# Enclosure_100x68_BHCP.net
KiCad netlist of a schematic drawn in EAGLE
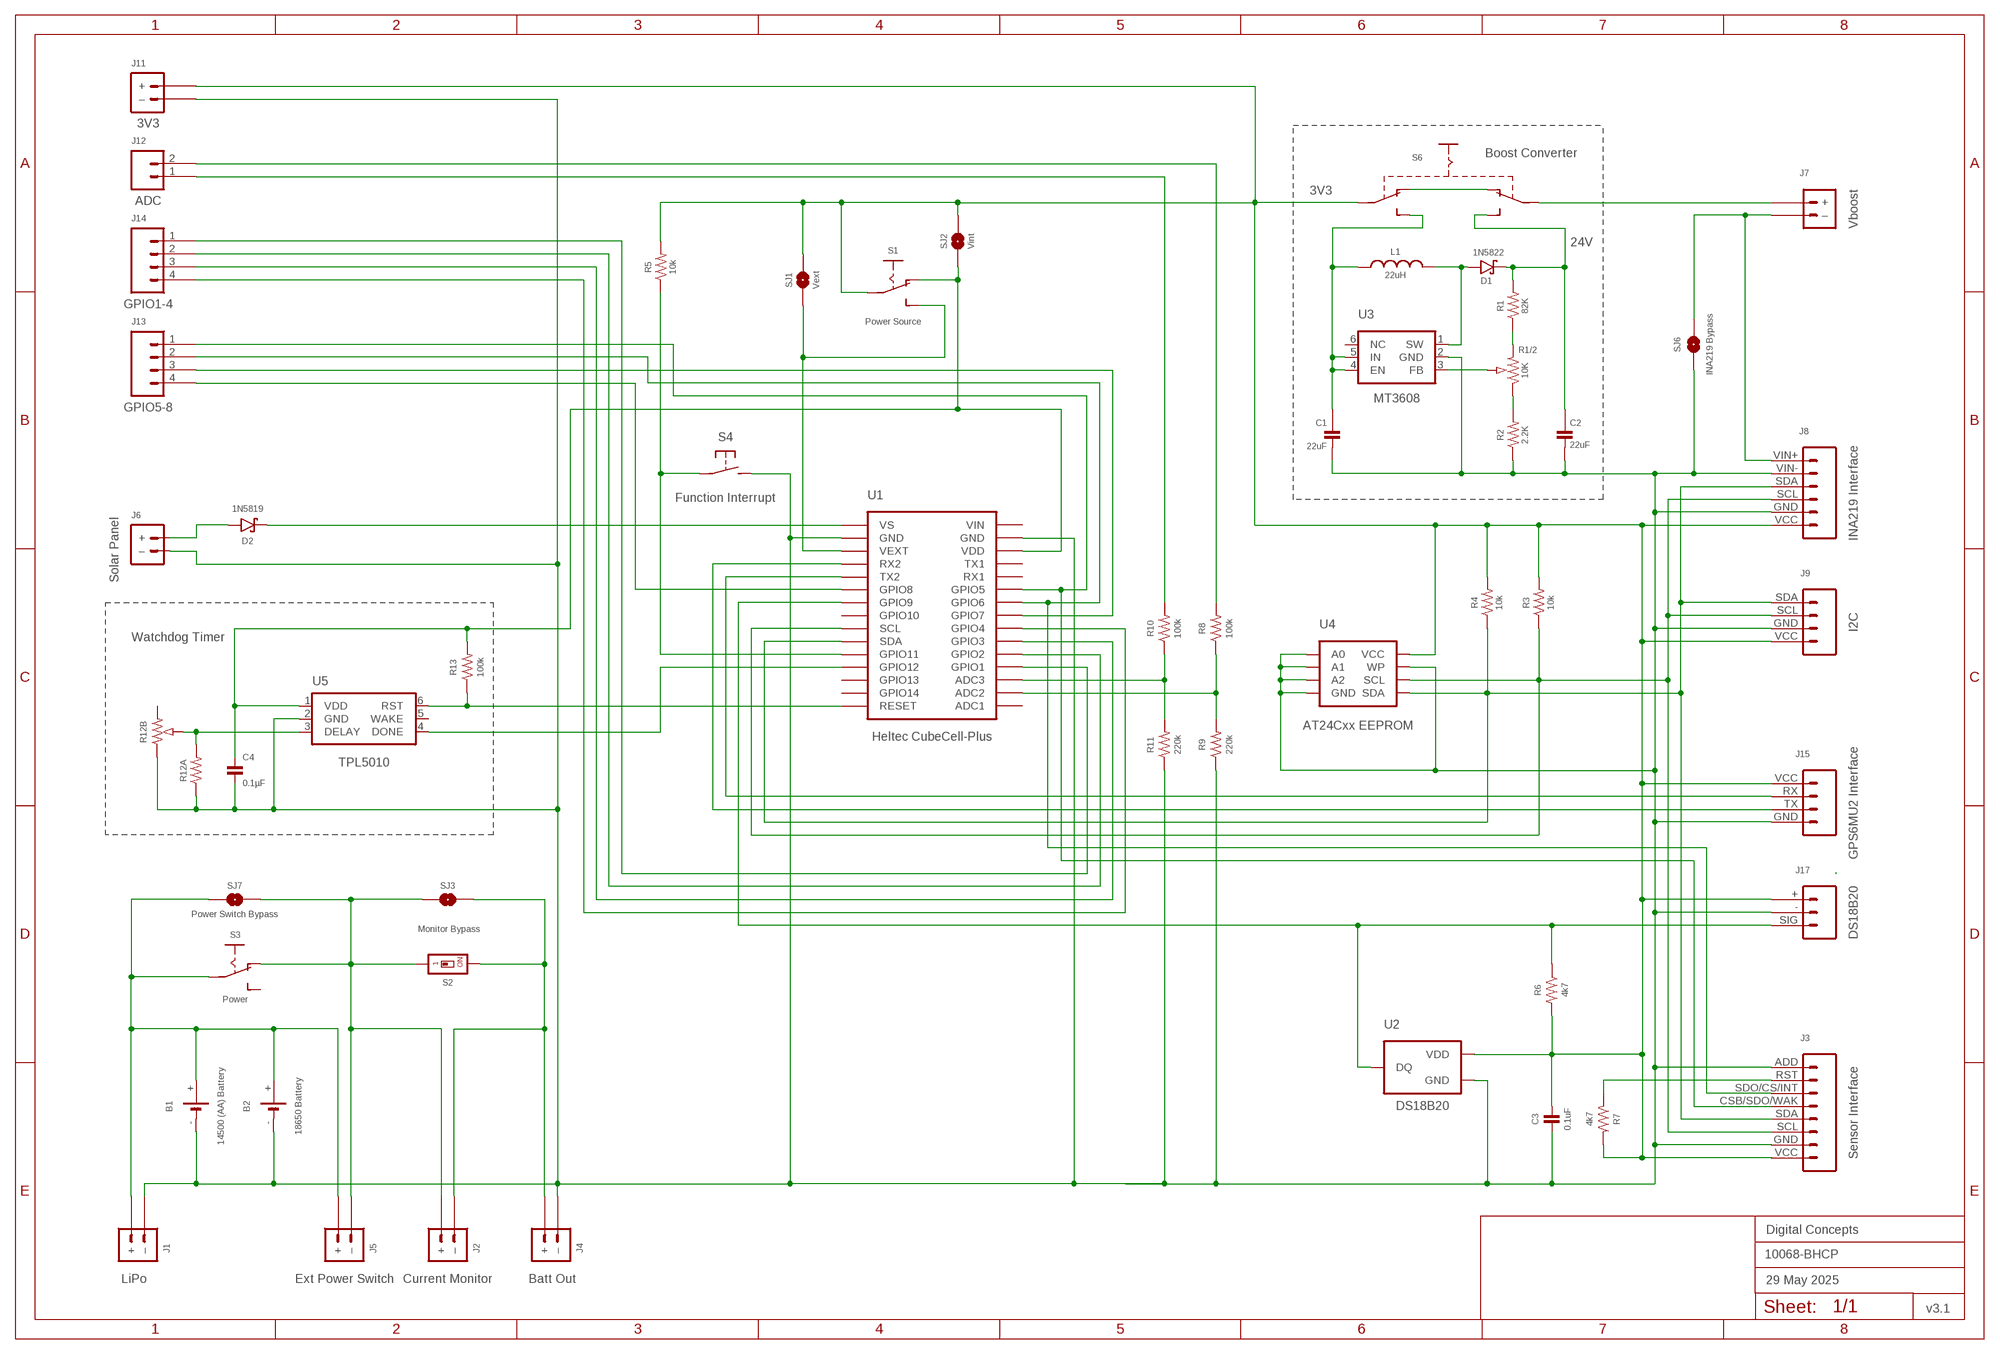
[diagram p0: schematic, sheet 1]

(export (version "E")
  (design (tool "Eeschema 10.0.6"))
  (components
    (comp (ref "B1")
      (value "14500 (AA) Battery")
      (footprint "eagle-import:BATTERY-14500")
      (libsource (lib "eagle-import") (part "BATTERY-HOLDER-14500(AA)"))
    )
    (comp (ref "B2")
      (value "18650 Battery")
      (footprint "eagle-import:BATTERY-18650")
      (libsource (lib "eagle-import") (part "BATTERY-HOLDER-18650"))
    )
    (comp (ref "C1")
      (value "22uF")
      (footprint "eagle-import:C1206")
      (libsource (lib "eagle-import") (part "CAPACITOR-1206"))
    )
    (comp (ref "C2")
      (value "22uF")
      (footprint "eagle-import:C1206")
      (libsource (lib "eagle-import") (part "CAPACITOR-1206"))
    )
    (comp (ref "C3")
      (value "0.1uF")
      (footprint "eagle-import:C0805")
      (libsource (lib "eagle-import") (part "CAPACITOR-0805"))
    )
    (comp (ref "C4")
      (value "0.1µF")
      (footprint "eagle-import:C0805")
      (libsource (lib "eagle-import") (part "CAPACITOR-0805"))
    )
    (comp (ref "D1")
      (value "1N5822")
      (footprint "eagle-import:DIODE_SMB")
      (libsource (lib "eagle-import") (part "DIODE-SCHOTTKY-1N5822"))
    )
    (comp (ref "D2")
      (value "1N5819")
      (footprint "eagle-import:SOD-123")
      (libsource (lib "eagle-import") (part "1N5819-SOD-123"))
    )
    (comp (ref "J1")
      (value "LiPo")
      (footprint "eagle-import:JST-PH2.0-2-HORIZONTAL-POWER")
      (libsource (lib "eagle-import") (part "JST-PH2.0-2-H-POWER"))
    )
    (comp (ref "J2")
      (value "Current Monitor")
      (footprint "eagle-import:JST-PH2.0-2-HORIZONTAL-POWER")
      (libsource (lib "eagle-import") (part "JST-PH2.0-2-H-POWER"))
    )
    (comp (ref "J3")
      (value "Sensor Interface")
      (footprint "eagle-import:CONN_08-SENSOR")
      (libsource (lib "eagle-import") (part "HEADER-1X8-SENSOR"))
    )
    (comp (ref "J4")
      (value "Batt Out")
      (footprint "eagle-import:JST-GH1.25-2-HORIZONTAL")
      (libsource (lib "eagle-import") (part "JST-GH1.25-2-HORIZONTAL-POWER"))
    )
    (comp (ref "J5")
      (value "Ext Power Switch")
      (footprint "eagle-import:JST-PH2.0-2-DUAL-POWER")
      (libsource (lib "eagle-import") (part "JST-PH2.0-2-DUAL-POWER{dblquote}"))
    )
    (comp (ref "J6")
      (value "Solar Panel")
      (footprint "eagle-import:JST-PH2.0-2-VERTICAL=POWER")
      (libsource (lib "eagle-import") (part "JST-PH2.0-2-VERTICAL"))
    )
    (comp (ref "J7")
      (value "Vboost")
      (footprint "eagle-import:JST-PH2.0-2-HORIZONTAL-POWER")
      (libsource (lib "eagle-import") (part "JST-PH2.0-2-H-POWER"))
    )
    (comp (ref "J8")
      (value "INA219 Interface")
      (footprint "eagle-import:CONN_06-INA219")
      (libsource (lib "eagle-import") (part "INA219-I2C-MODULE"))
    )
    (comp (ref "J9")
      (value "I2C")
      (footprint "eagle-import:JST-PH2.0-4-HORIZONTAL@1")
      (libsource (lib "eagle-import") (part "JST-PH2.0-I2C-MALE-HORIZONTAL"))
    )
    (comp (ref "J11")
      (value "3V3")
      (footprint "eagle-import:JST-PH2.0-2-HORIZONTAL-POWER")
      (libsource (lib "eagle-import") (part "JST-PH2.0-2-H-POWER"))
    )
    (comp (ref "J12")
      (value "ADC")
      (footprint "eagle-import:JST-PH2.0-2-HORIZONTAL")
      (libsource (lib "eagle-import") (part "JST-PH2.0-2-HORIZONTAL"))
    )
    (comp (ref "J13")
      (value "GPIO5-8")
      (footprint "eagle-import:JST-PH2.0-4-HORIZONTAL")
      (libsource (lib "eagle-import") (part "JST-PH2.0-4-HORIZONTAL"))
    )
    (comp (ref "J14")
      (value "GPIO1-4")
      (footprint "eagle-import:JST-PH2.0-4-HORIZONTAL")
      (libsource (lib "eagle-import") (part "JST-PH2.0-4-HORIZONTAL"))
    )
    (comp (ref "J15")
      (value "GPS6MU2 Interface")
      (footprint "eagle-import:CONN_04-GPS")
      (libsource (lib "eagle-import") (part "HEADER-1X4-GPS"))
    )
    (comp (ref "J17")
      (value "DS18B20")
      (footprint "eagle-import:JST-PH2.0-DS18B20-HORIZONTAL")
      (libsource (lib "eagle-import") (part "JST-PH2.0-3-HORIZONTAL-DS18B20"))
    )
    (comp (ref "L1")
      (value "22uH")
      (footprint "eagle-import:CDRH104R+6D28")
      (libsource (lib "eagle-import") (part "INDUCTOR-CDRH104R/6D28L5038P"))
    )
    (comp (ref "R1")
      (value "82K")
      (footprint "eagle-import:R0805")
      (libsource (lib "eagle-import") (part "RESISTORR0805"))
    )
    (comp (ref "R1/2")
      (value "10K")
      (footprint "eagle-import:RTRIM64P")
      (libsource (lib "eagle-import") (part "RESISTOR-TRIMM-BAOTER-H-US"))
    )
    (comp (ref "R2")
      (value "2.2K")
      (footprint "eagle-import:R0805")
      (libsource (lib "eagle-import") (part "RESISTORR0805"))
    )
    (comp (ref "R3")
      (value "10k")
      (footprint "eagle-import:R0805")
      (libsource (lib "eagle-import") (part "RESISTORR0805"))
    )
    (comp (ref "R4")
      (value "10k")
      (footprint "eagle-import:R0805")
      (libsource (lib "eagle-import") (part "RESISTORR0805"))
    )
    (comp (ref "R5")
      (value "10k")
      (footprint "eagle-import:R0805")
      (libsource (lib "eagle-import") (part "RESISTORR0805"))
    )
    (comp (ref "R6")
      (value "4k7")
      (footprint "eagle-import:R0805")
      (libsource (lib "eagle-import") (part "RESISTORR0805"))
    )
    (comp (ref "R7")
      (value "4k7")
      (footprint "eagle-import:R0805")
      (libsource (lib "eagle-import") (part "RESISTORR0805"))
    )
    (comp (ref "R8")
      (value "100k")
      (footprint "eagle-import:R0805")
      (libsource (lib "eagle-import") (part "RESISTORR0805"))
    )
    (comp (ref "R9")
      (value "220k")
      (footprint "eagle-import:R0805")
      (libsource (lib "eagle-import") (part "RESISTORR0805"))
    )
    (comp (ref "R10")
      (value "100k")
      (footprint "eagle-import:R0805")
      (libsource (lib "eagle-import") (part "RESISTORR0805"))
    )
    (comp (ref "R11")
      (value "220k")
      (footprint "eagle-import:R0805")
      (libsource (lib "eagle-import") (part "RESISTORR0805"))
    )
    (comp (ref "R12A")
      (value "RESISTORR0805")
      (footprint "eagle-import:R0805")
      (libsource (lib "eagle-import") (part "RESISTORR0805"))
    )
    (comp (ref "R12B")
      (value "RESISTOR-TRIMM-33-US")
      (footprint "eagle-import:RTRIM3_3")
      (libsource (lib "eagle-import") (part "RESISTOR-TRIMM-33-US"))
    )
    (comp (ref "R13")
      (value "100k")
      (footprint "eagle-import:R0805")
      (libsource (lib "eagle-import") (part "RESISTORR0805"))
    )
    (comp (ref "S1")
      (value "Power Source")
      (footprint "eagle-import:SWITCH-SPDT-SMT")
      (libsource (lib "eagle-import") (part "SWITCH-SLIDE-SPDT-SMT"))
    )
    (comp (ref "S2")
      (value "Monitor Bypass")
      (footprint "eagle-import:SMD-001")
      (libsource (lib "eagle-import") (part "SWITCH-DIP-SWS001"))
    )
    (comp (ref "S3")
      (value "Power")
      (footprint "eagle-import:SWITCH-SPDT-PTH")
      (libsource (lib "eagle-import") (part "SWITCH-SLIDE-SPDT-PTH"))
    )
    (comp (ref "S4")
      (value "Function Interrupt")
      (footprint "eagle-import:SWITCH-2-PAD")
      (libsource (lib "eagle-import") (part "SWITCH-MOMENTARY-2-PIN"))
    )
    (comp (ref "S6")
      (value "SWITCH-SLIDE-DPDT-PTH-S")
      (footprint "eagle-import:SWITCH-DPDT-PTH")
      (libsource (lib "eagle-import") (part "SWITCH-SLIDE-DPDT-PTH-S"))
    )
    (comp (ref "SJ1")
      (value "Vext")
      (footprint "eagle-import:SJ")
      (libsource (lib "eagle-import") (part "SJ"))
    )
    (comp (ref "SJ2")
      (value "Vint")
      (footprint "eagle-import:SJ-VIA-12")
      (libsource (lib "eagle-import") (part "SJ-V-12"))
    )
    (comp (ref "SJ3")
      (value "Monitor")
      (footprint "eagle-import:SJ")
      (libsource (lib "eagle-import") (part "SJ"))
    )
    (comp (ref "SJ6")
      (value "INA219 Bypass")
      (footprint "eagle-import:SJ")
      (libsource (lib "eagle-import") (part "SJ"))
    )
    (comp (ref "SJ7")
      (value "Power Switch Bypass")
      (footprint "eagle-import:SJ")
      (libsource (lib "eagle-import") (part "SJ"))
    )
    (comp (ref "U1")
      (value "Heltec CubeCell-Plus")
      (footprint "eagle-import:HELTEC-CUBECELL=PLUS-X")
      (libsource (lib "eagle-import") (part "HELTEC-CUBECELL-PLUS-X"))
    )
    (comp (ref "U2")
      (value "DS18B20")
      (footprint "eagle-import:TO-92")
      (fields (field (name "MF") "Maxim Integrated"))
      (libsource (lib "eagle-import") (part "THERMOMETER-DS18B20"))
    )
    (comp (ref "U3")
      (value "MT3608")
      (footprint "eagle-import:SOT-23-6")
      (libsource (lib "eagle-import") (part "MT3608"))
    )
    (comp (ref "U4")
      (value "AT24Cxx EEPROM")
      (footprint "eagle-import:SOP-8")
      (libsource (lib "eagle-import") (part "AT24CXX-EEPROM"))
    )
    (comp (ref "U5")
      (value "TPL5010")
      (footprint "eagle-import:SOT-23-6")
      (libsource (lib "eagle-import") (part "TPL5010DDCR"))
    )
  )
  (nets
    (net (code "1") (name "/VIN") (class "Default")
      (node (ref "U1") (pin "VIN") (pinfunction "VIN_VIN") (pintype "power_in"))
    )
    (net (code "2") (name "Net-(D2-PadA)") (class "Default")
      (node (ref "D2") (pin "A") (pinfunction "A_A") (pintype "passive"))
      (node (ref "J6") (pin "+") (pinfunction "+_+") (pintype "power_in"))
    )
    (net (code "3") (name "Net-(D2-PadC)") (class "Default")
      (node (ref "D2") (pin "C") (pinfunction "C_C") (pintype "passive"))
      (node (ref "U1") (pin "VS") (pinfunction "VS_VS") (pintype "power_in"))
    )
    (net (code "4") (name "Net-(J1-–)") (class "Default")
      (node (ref "B1") (pin "-") (pinfunction "-_-") (pintype "power_in"))
      (node (ref "B2") (pin "-") (pinfunction "-_-") (pintype "power_in"))
      (node (ref "C1") (pin "2") (pinfunction "2_2") (pintype "passive"))
      (node (ref "C2") (pin "2") (pinfunction "2_2") (pintype "passive"))
      (node (ref "C3") (pin "2") (pinfunction "2_2") (pintype "passive"))
      (node (ref "C4") (pin "2") (pinfunction "2_2") (pintype "passive"))
      (node (ref "J1") (pin "-") (pinfunction "–_-") (pintype "power_in"))
      (node (ref "J11") (pin "-") (pinfunction "–_-") (pintype "power_in"))
      (node (ref "J15") (pin "GND") (pinfunction "1_GND") (pintype "passive"))
      (node (ref "J17") (pin "-") (pinfunction "2_-") (pintype "passive"))
      (node (ref "J3") (pin "ADD") (pinfunction "8_ADD") (pintype "passive"))
      (node (ref "J3") (pin "GND") (pinfunction "2_GND") (pintype "passive"))
      (node (ref "J4") (pin "-") (pinfunction "–_-") (pintype "power_in"))
      (node (ref "J6") (pin "-") (pinfunction "–_-") (pintype "power_in"))
      (node (ref "J8") (pin "GND") (pinfunction "2_GND") (pintype "passive"))
      (node (ref "J8") (pin "VIN-") (pinfunction "5_VIN-") (pintype "passive"))
      (node (ref "J9") (pin "GND") (pinfunction "2_GND") (pintype "passive"))
      (node (ref "R11") (pin "1") (pinfunction "1_1") (pintype "passive"))
      (node (ref "R12A") (pin "1") (pinfunction "1_1") (pintype "passive"))
      (node (ref "R12B") (pin "1") (pinfunction "A_1") (pintype "passive"))
      (node (ref "R2") (pin "1") (pinfunction "1_1") (pintype "passive"))
      (node (ref "R9") (pin "1") (pinfunction "1_1") (pintype "passive"))
      (node (ref "S4") (pin "P$2") (pinfunction "S_P$2") (pintype "passive"))
      (node (ref "SJ6") (pin "1") (pinfunction "1_1") (pintype "passive"))
      (node (ref "U1") (pin "GND@14") (pinfunction "GND_GND@14") (pintype "power_in"))
      (node (ref "U1") (pin "GND@17") (pinfunction "GND_GND@17") (pintype "power_in"))
      (node (ref "U2") (pin "1") (pinfunction "GND_1") (pintype "power_in"))
      (node (ref "U3") (pin "2") (pinfunction "GND_2") (pintype "power_in"))
      (node (ref "U4") (pin "P$1") (pinfunction "A0_P$1") (pintype "bidirectional"))
      (node (ref "U4") (pin "P$2") (pinfunction "A1_P$2") (pintype "bidirectional"))
      (node (ref "U4") (pin "P$3") (pinfunction "A2_P$3") (pintype "bidirectional"))
      (node (ref "U4") (pin "P$4") (pinfunction "GND_P$4") (pintype "bidirectional"))
      (node (ref "U4") (pin "P$7") (pinfunction "WP_P$7") (pintype "bidirectional"))
      (node (ref "U5") (pin "2") (pinfunction "GND_2") (pintype "power_in"))
    )
    (net (code "5") (name "Net-(J2-–)") (class "Default")
      (node (ref "J2") (pin "-") (pinfunction "–_-") (pintype "power_in"))
      (node (ref "J4") (pin "+") (pinfunction "+_+") (pintype "power_in"))
      (node (ref "S2") (pin "2") (pinfunction "2_2") (pintype "passive"))
      (node (ref "SJ3") (pin "1") (pinfunction "1_1") (pintype "passive"))
    )
    (net (code "6") (name "Net-(J3-3)") (class "Default")
      (node (ref "J3") (pin "SCL") (pinfunction "3_SCL") (pintype "passive"))
      (node (ref "J8") (pin "SCL") (pinfunction "3_SCL") (pintype "passive"))
      (node (ref "J9") (pin "SCL") (pinfunction "3_SCL") (pintype "passive"))
      (node (ref "R3") (pin "1") (pinfunction "1_1") (pintype "passive"))
      (node (ref "U1") (pin "SCL") (pinfunction "SCL_SCL") (pintype "bidirectional"))
      (node (ref "U4") (pin "P$6") (pinfunction "SCL_P$6") (pintype "bidirectional"))
    )
    (net (code "7") (name "Net-(J3-4)") (class "Default")
      (node (ref "J3") (pin "SDA") (pinfunction "4_SDA") (pintype "passive"))
      (node (ref "J8") (pin "SDA") (pinfunction "4_SDA") (pintype "passive"))
      (node (ref "J9") (pin "SDA") (pinfunction "4_SDA") (pintype "passive"))
      (node (ref "R4") (pin "1") (pinfunction "1_1") (pintype "passive"))
      (node (ref "U1") (pin "SDA") (pinfunction "SDA_SDA") (pintype "bidirectional"))
      (node (ref "U4") (pin "P$5") (pinfunction "SDA_P$5") (pintype "bidirectional"))
    )
    (net (code "8") (name "Net-(J3-7)") (class "Default")
      (node (ref "J3") (pin "RST") (pinfunction "7_RST") (pintype "passive"))
      (node (ref "R7") (pin "1") (pinfunction "1_1") (pintype "passive"))
    )
    (net (code "9") (name "Net-(J5-–)") (class "Default")
      (node (ref "J2") (pin "+") (pinfunction "+_+") (pintype "power_in"))
      (node (ref "J5") (pin "-") (pinfunction "–_-") (pintype "power_in"))
      (node (ref "S2") (pin "1") (pinfunction "1_1") (pintype "passive"))
      (node (ref "S3") (pin "1") (pinfunction "O_1") (pintype "passive"))
      (node (ref "SJ3") (pin "2") (pinfunction "2_2") (pintype "passive"))
      (node (ref "SJ7") (pin "1") (pinfunction "1_1") (pintype "passive"))
    )
    (net (code "10") (name "Net-(J7-–)") (class "Default")
      (node (ref "J7") (pin "-") (pinfunction "–_-") (pintype "power_in"))
      (node (ref "J8") (pin "VIN+") (pinfunction "6_VIN+") (pintype "passive"))
      (node (ref "SJ6") (pin "2") (pinfunction "2_2") (pintype "passive"))
    )
    (net (code "11") (name "Net-(J12-Pad1)") (class "Default")
      (node (ref "J12") (pin "1") (pinfunction "1_1") (pintype "passive"))
      (node (ref "R10") (pin "2") (pinfunction "2_2") (pintype "passive"))
    )
    (net (code "12") (name "Net-(J12-Pad2)") (class "Default")
      (node (ref "J12") (pin "2") (pinfunction "2_2") (pintype "passive"))
      (node (ref "R8") (pin "2") (pinfunction "2_2") (pintype "passive"))
    )
    (net (code "13") (name "Net-(J13-1)") (class "Default")
      (node (ref "J13") (pin "4") (pinfunction "1_4") (pintype "passive"))
      (node (ref "U1") (pin "GPIO8") (pinfunction "GPIO8_GPIO8") (pintype "bidirectional"))
    )
    (net (code "14") (name "Net-(J13-2)") (class "Default")
      (node (ref "J13") (pin "3") (pinfunction "2_3") (pintype "passive"))
      (node (ref "U1") (pin "GPIO7") (pinfunction "GPIO7_GPIO7") (pintype "bidirectional"))
    )
    (net (code "15") (name "Net-(J13-3)") (class "Default")
      (node (ref "J13") (pin "2") (pinfunction "3_2") (pintype "passive"))
      (node (ref "J3") (pin "SDO/CS/INT") (pinfunction "6_SDO/CS/INT") (pintype "passive"))
      (node (ref "U1") (pin "GPIO6") (pinfunction "GPIO6_GPIO6") (pintype "bidirectional"))
    )
    (net (code "16") (name "Net-(J13-4)") (class "Default")
      (node (ref "J13") (pin "1") (pinfunction "4_1") (pintype "passive"))
      (node (ref "J3") (pin "CSB/SDO/WAK") (pinfunction "5_CSB/SDO/WAK") (pintype "passive"))
      (node (ref "U1") (pin "GPIO5") (pinfunction "GPIO5_GPIO5") (pintype "bidirectional"))
    )
    (net (code "17") (name "Net-(J14-1)") (class "Default")
      (node (ref "J14") (pin "4") (pinfunction "1_4") (pintype "passive"))
      (node (ref "U1") (pin "GPIO4") (pinfunction "GPIO4_GPIO4") (pintype "bidirectional"))
    )
    (net (code "18") (name "Net-(J14-2)") (class "Default")
      (node (ref "J14") (pin "3") (pinfunction "2_3") (pintype "passive"))
      (node (ref "U1") (pin "GPIO3") (pinfunction "GPIO3_GPIO3") (pintype "bidirectional"))
    )
    (net (code "19") (name "Net-(J14-3)") (class "Default")
      (node (ref "J14") (pin "2") (pinfunction "3_2") (pintype "passive"))
      (node (ref "U1") (pin "GPIO2") (pinfunction "GPIO2_GPIO2") (pintype "bidirectional"))
    )
    (net (code "20") (name "Net-(J14-4)") (class "Default")
      (node (ref "J14") (pin "1") (pinfunction "4_1") (pintype "passive"))
      (node (ref "U1") (pin "GPIO1") (pinfunction "GPIO1_GPIO1") (pintype "bidirectional"))
    )
    (net (code "21") (name "Net-(J15-2)") (class "Default")
      (node (ref "J15") (pin "TX") (pinfunction "2_TX") (pintype "passive"))
      (node (ref "U1") (pin "RX2") (pinfunction "RX2_RX2") (pintype "bidirectional"))
    )
    (net (code "22") (name "Net-(J15-3)") (class "Default")
      (node (ref "J15") (pin "RX") (pinfunction "3_RX") (pintype "passive"))
      (node (ref "U1") (pin "TX2") (pinfunction "TX2_TX2") (pintype "bidirectional"))
    )
    (net (code "23") (name "Net-(J15-4)") (class "Default")
      (node (ref "C3") (pin "1") (pinfunction "1_1") (pintype "passive"))
      (node (ref "J11") (pin "+") (pinfunction "+_+") (pintype "power_in"))
      (node (ref "J15") (pin "VCC") (pinfunction "4_VCC") (pintype "passive"))
      (node (ref "J17") (pin "+") (pinfunction "3_+") (pintype "passive"))
      (node (ref "J3") (pin "VCC") (pinfunction "1_VCC") (pintype "passive"))
      (node (ref "J8") (pin "VCC") (pinfunction "1_VCC") (pintype "passive"))
      (node (ref "J9") (pin "VCC") (pinfunction "1_VCC") (pintype "passive"))
      (node (ref "R3") (pin "2") (pinfunction "2_2") (pintype "passive"))
      (node (ref "R4") (pin "2") (pinfunction "2_2") (pintype "passive"))
      (node (ref "R5") (pin "2") (pinfunction "2_2") (pintype "passive"))
      (node (ref "R6") (pin "2") (pinfunction "2_2") (pintype "passive"))
      (node (ref "R7") (pin "2") (pinfunction "2_2") (pintype "passive"))
      (node (ref "S1") (pin "2") (pinfunction "P_2") (pintype "passive"))
      (node (ref "S6") (pin "P$5") (pinfunction "P2_P$5") (pintype "passive"))
      (node (ref "SJ1") (pin "2") (pinfunction "2_2") (pintype "passive"))
      (node (ref "SJ2") (pin "2") (pinfunction "2_2") (pintype "passive"))
      (node (ref "SJ2") (pin "2@V") (pinfunction "2_2@V") (pintype "passive"))
      (node (ref "U2") (pin "3") (pinfunction "VDD_3") (pintype "power_in"))
      (node (ref "U4") (pin "P$8") (pinfunction "VCC_P$8") (pintype "bidirectional"))
    )
    (net (code "24") (name "Net-(J17-1)") (class "Default")
      (node (ref "J17") (pin "SIG") (pinfunction "1_SIG") (pintype "passive"))
      (node (ref "R6") (pin "1") (pinfunction "1_1") (pintype "passive"))
      (node (ref "U1") (pin "GPIO9") (pinfunction "GPIO9_GPIO9") (pintype "bidirectional"))
      (node (ref "U2") (pin "2") (pinfunction "DQ_2") (pintype "bidirectional"))
    )
    (net (code "25") (name "Net-(R1/2-A)") (class "Default")
      (node (ref "R1/2") (pin "1") (pinfunction "A_1") (pintype "passive"))
      (node (ref "R2") (pin "2") (pinfunction "2_2") (pintype "passive"))
    )
    (net (code "26") (name "Net-(R1/2-E)") (class "Default")
      (node (ref "R1") (pin "1") (pinfunction "1_1") (pintype "passive"))
      (node (ref "R1/2") (pin "3") (pinfunction "E_3") (pintype "passive"))
    )
    (net (code "27") (name "Net-(R1/2-S)") (class "Default")
      (node (ref "R1/2") (pin "2") (pinfunction "S_2") (pintype "passive"))
      (node (ref "U3") (pin "3") (pinfunction "FB_3") (pintype "input"))
    )
    (net (code "28") (name "Net-(R8-Pad1)") (class "Default")
      (node (ref "R8") (pin "1") (pinfunction "1_1") (pintype "passive"))
      (node (ref "R9") (pin "2") (pinfunction "2_2") (pintype "passive"))
      (node (ref "U1") (pin "ADC2") (pinfunction "ADC2_ADC2") (pintype "bidirectional"))
    )
    (net (code "29") (name "Net-(R10-Pad1)") (class "Default")
      (node (ref "R10") (pin "1") (pinfunction "1_1") (pintype "passive"))
      (node (ref "R11") (pin "2") (pinfunction "2_2") (pintype "passive"))
      (node (ref "U1") (pin "ADC3") (pinfunction "ADC3_ADC3") (pintype "bidirectional"))
    )
    (net (code "30") (name "Net-(R12B-S)") (class "Default")
      (node (ref "R12A") (pin "2") (pinfunction "2_2") (pintype "passive"))
      (node (ref "R12B") (pin "2") (pinfunction "S_2") (pintype "passive"))
      (node (ref "U5") (pin "3") (pinfunction "DELAY_3") (pintype "input"))
    )
    (net (code "31") (name "Net-(S1-O)") (class "Default")
      (node (ref "C4") (pin "1") (pinfunction "1_1") (pintype "passive"))
      (node (ref "R13") (pin "2") (pinfunction "2_2") (pintype "passive"))
      (node (ref "S1") (pin "1") (pinfunction "O_1") (pintype "passive"))
      (node (ref "SJ2") (pin "1") (pinfunction "1_1") (pintype "passive"))
      (node (ref "SJ2") (pin "1@V") (pinfunction "1_1@V") (pintype "passive"))
      (node (ref "U1") (pin "VDD") (pinfunction "VDD_VDD") (pintype "power_in"))
      (node (ref "U5") (pin "1") (pinfunction "VDD_1") (pintype "power_in"))
    )
    (net (code "32") (name "Net-(S1-S)") (class "Default")
      (node (ref "S1") (pin "3") (pinfunction "S_3") (pintype "passive"))
      (node (ref "SJ1") (pin "1") (pinfunction "1_1") (pintype "passive"))
      (node (ref "U1") (pin "VEXT") (pinfunction "VEXT_VEXT") (pintype "power_in"))
    )
    (net (code "33") (name "Net-(S3-P)") (class "Default")
      (node (ref "B1") (pin "+") (pinfunction "+_+") (pintype "power_in"))
      (node (ref "B2") (pin "+") (pinfunction "+_+") (pintype "power_in"))
      (node (ref "J1") (pin "+") (pinfunction "+_+") (pintype "power_in"))
      (node (ref "J5") (pin "+") (pinfunction "+_+") (pintype "power_in"))
      (node (ref "S3") (pin "2") (pinfunction "P_2") (pintype "passive"))
      (node (ref "SJ7") (pin "2") (pinfunction "2_2") (pintype "passive"))
    )
    (net (code "34") (name "Net-(S4-P)") (class "Default")
      (node (ref "R5") (pin "1") (pinfunction "1_1") (pintype "passive"))
      (node (ref "S4") (pin "P$1") (pinfunction "P_P$1") (pintype "passive"))
      (node (ref "U1") (pin "GPIO11") (pinfunction "GPIO11_GPIO11") (pintype "bidirectional"))
    )
    (net (code "35") (name "Net-(S6-O1)") (class "Default")
      (node (ref "S6") (pin "P$1") (pinfunction "O1_P$1") (pintype "passive"))
      (node (ref "S6") (pin "P$4") (pinfunction "O2_P$4") (pintype "passive"))
    )
    (net (code "36") (name "Net-(S6-P1)") (class "Default")
      (node (ref "J7") (pin "+") (pinfunction "+_+") (pintype "power_in"))
      (node (ref "S6") (pin "P$2") (pinfunction "P1_P$2") (pintype "passive"))
    )
    (net (code "37") (name "Net-(S6-S1)") (class "Default")
      (node (ref "C2") (pin "1") (pinfunction "1_1") (pintype "passive"))
      (node (ref "D1") (pin "C") (pinfunction "C_C") (pintype "passive"))
      (node (ref "R1") (pin "2") (pinfunction "2_2") (pintype "passive"))
      (node (ref "S6") (pin "P$3") (pinfunction "S1_P$3") (pintype "passive"))
    )
    (net (code "38") (name "Net-(S6-S2)") (class "Default")
      (node (ref "C1") (pin "1") (pinfunction "1_1") (pintype "passive"))
      (node (ref "L1") (pin "2") (pinfunction "2_2") (pintype "passive"))
      (node (ref "S6") (pin "P$6") (pinfunction "S2_P$6") (pintype "passive"))
      (node (ref "U3") (pin "4") (pinfunction "EN_4") (pintype "input"))
      (node (ref "U3") (pin "5") (pinfunction "IN_5") (pintype "power_in"))
    )
    (net (code "39") (name "Net-(U1-RESET)") (class "Default")
      (node (ref "R13") (pin "1") (pinfunction "1_1") (pintype "passive"))
      (node (ref "U1") (pin "RST") (pinfunction "RESET_RST") (pintype "bidirectional"))
      (node (ref "U5") (pin "6") (pinfunction "RST_6") (pintype "output"))
    )
    (net (code "40") (name "Net-(U3-SW)") (class "Default")
      (node (ref "D1") (pin "A") (pinfunction "A_A") (pintype "passive"))
      (node (ref "L1") (pin "1") (pinfunction "1_1") (pintype "passive"))
      (node (ref "U3") (pin "1") (pinfunction "SW_1") (pintype "power_in"))
    )
    (net (code "41") (name "Net-(U5-DONE)") (class "Default")
      (node (ref "U1") (pin "GPIO12") (pinfunction "GPIO12_GPIO12") (pintype "bidirectional"))
      (node (ref "U5") (pin "4") (pinfunction "DONE_4") (pintype "input"))
    )
    (net (code "42") (name "unconnected-(R12B-E-Pad3)") (class "Default")
      (node (ref "R12B") (pin "3") (pinfunction "E_3") (pintype "passive"))
    )
    (net (code "43") (name "unconnected-(S3-S-Pad3)") (class "Default")
      (node (ref "S3") (pin "3") (pinfunction "S_3") (pintype "passive"))
    )
    (net (code "44") (name "unconnected-(U1-PadADC1)") (class "Default")
      (node (ref "U1") (pin "ADC1") (pinfunction "ADC1_ADC1") (pintype "bidirectional"))
    )
    (net (code "45") (name "unconnected-(U1-PadGPIO10)") (class "Default")
      (node (ref "U1") (pin "GPIO10") (pinfunction "GPIO10_GPIO10") (pintype "bidirectional"))
    )
    (net (code "46") (name "unconnected-(U1-PadGPIO13)") (class "Default")
      (node (ref "U1") (pin "GPIO13") (pinfunction "GPIO13_GPIO13") (pintype "bidirectional"))
    )
    (net (code "47") (name "unconnected-(U1-PadGPIO14)") (class "Default")
      (node (ref "U1") (pin "GPIO14") (pinfunction "GPIO14_GPIO14") (pintype "bidirectional"))
    )
    (net (code "48") (name "unconnected-(U1-PadRX1)") (class "Default")
      (node (ref "U1") (pin "RX1") (pinfunction "RX1_RX1") (pintype "bidirectional"))
    )
    (net (code "49") (name "unconnected-(U1-PadTX1)") (class "Default")
      (node (ref "U1") (pin "TX1") (pinfunction "TX1_TX1") (pintype "bidirectional"))
    )
    (net (code "50") (name "unconnected-(U3-NC-Pad6)") (class "Default")
      (node (ref "U3") (pin "6") (pinfunction "NC_6") (pintype "no_connect"))
    )
    (net (code "51") (name "unconnected-(U5-WAKE-Pad5)") (class "Default")
      (node (ref "U5") (pin "5") (pinfunction "WAKE_5") (pintype "output"))
    )
  )
)
